# untitled.net
KiCad netlist of a schematic drawn in EAGLE
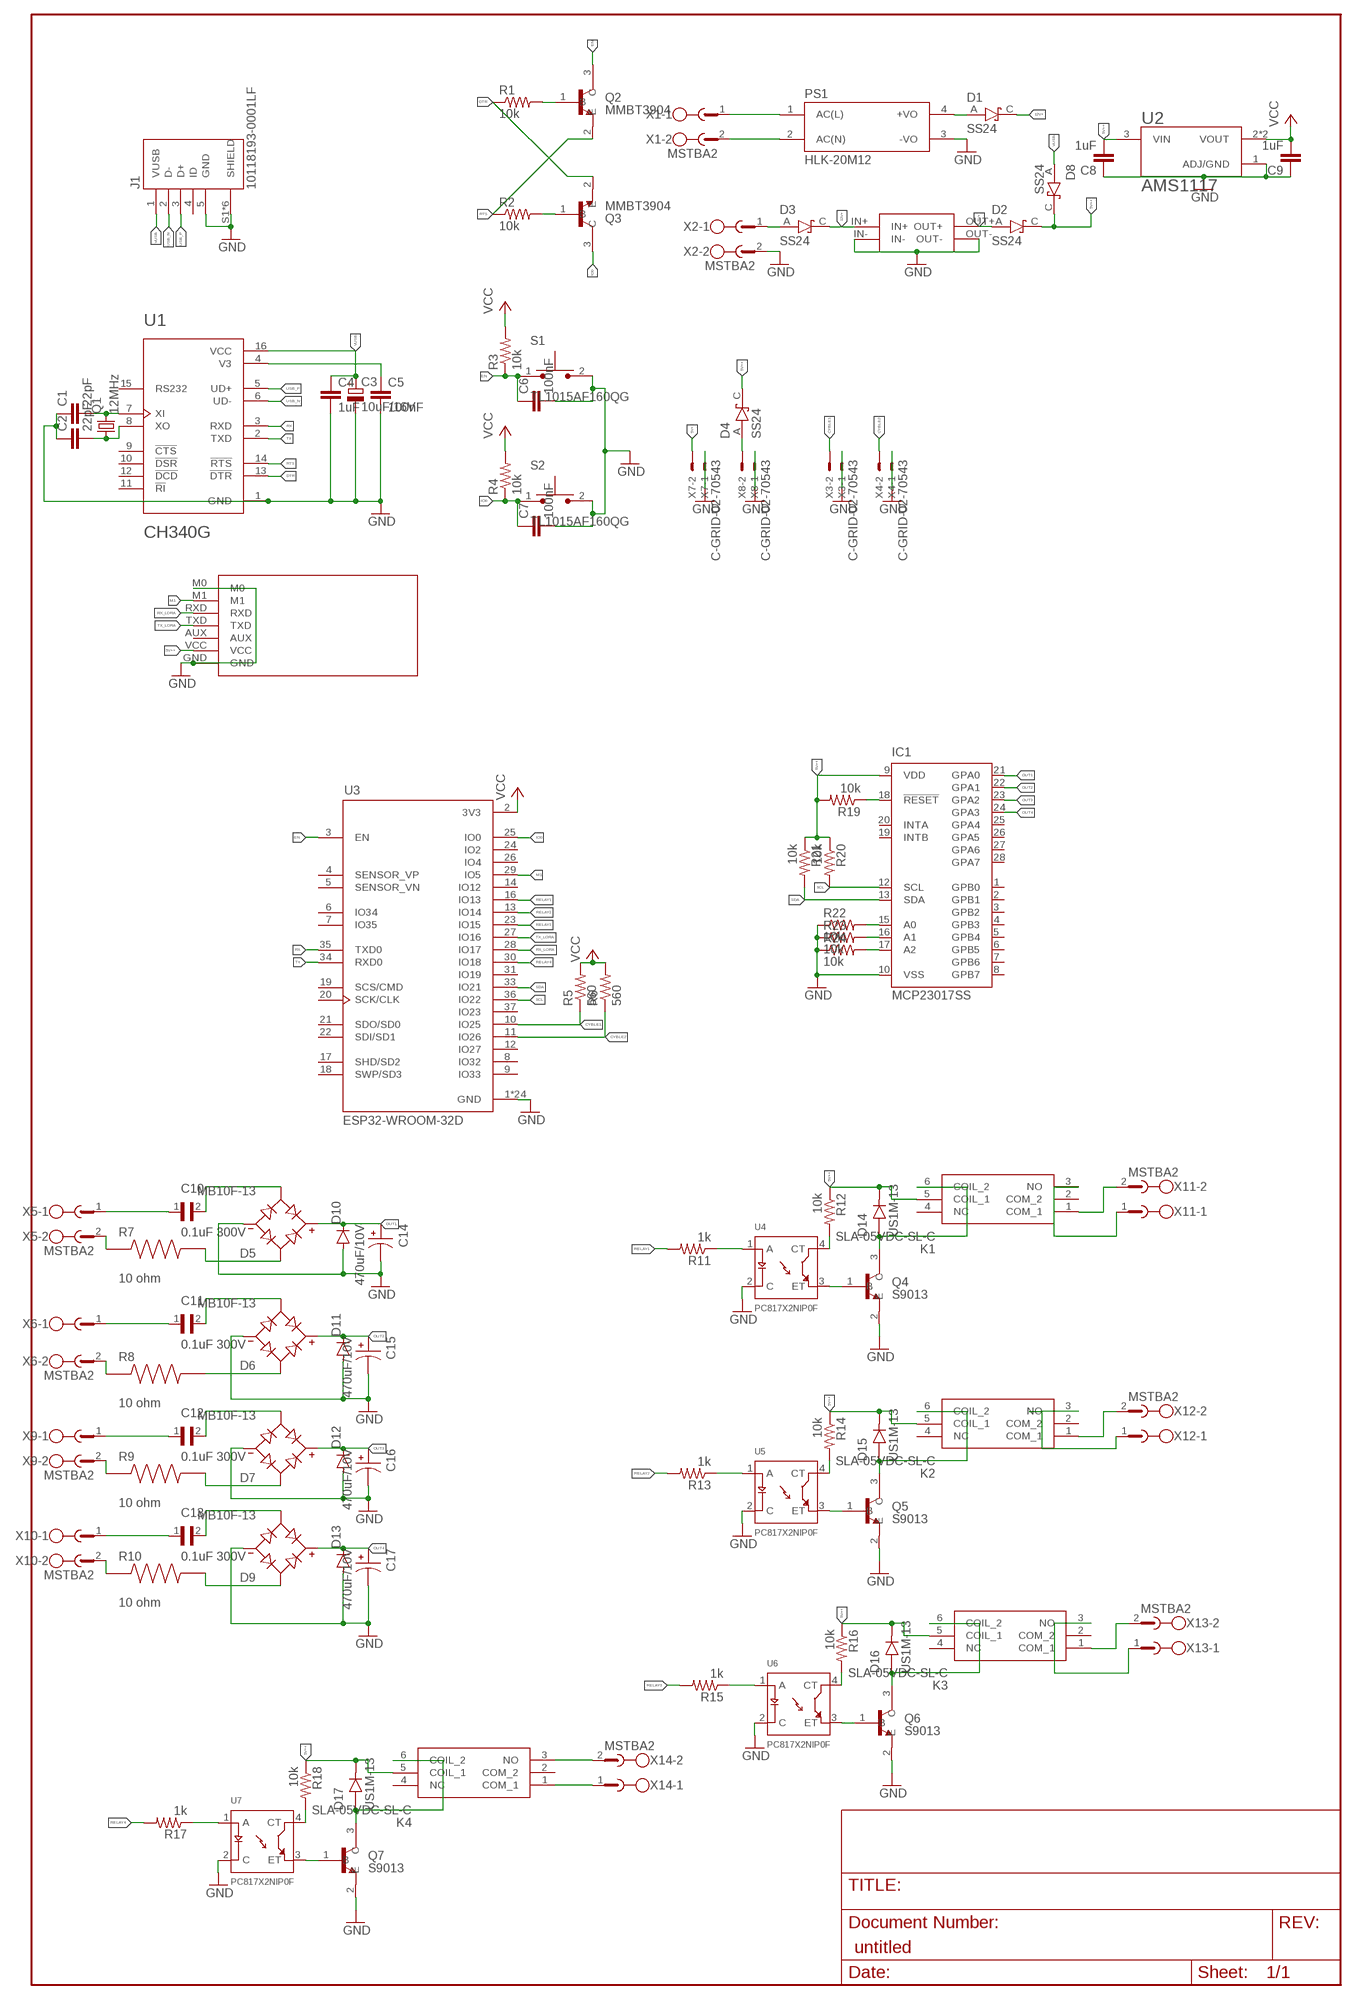
[diagram p0: schematic, sheet 1]

(export (version "E")
  (design (tool "Eeschema 10.0.6"))
  (components
    (comp (ref "C1")
      (value "22pF")
      (footprint "eagle-import:C0805K")
      (libsource (lib "eagle-import") (part "C-EUC0805K"))
    )
    (comp (ref "C2")
      (value "22pF")
      (footprint "eagle-import:C0805K")
      (libsource (lib "eagle-import") (part "C-EUC0805K"))
    )
    (comp (ref "C3")
      (value "10uF/16V")
      (footprint "eagle-import:153CLV-0505")
      (libsource (lib "eagle-import") (part "CPOL-EU153CLV-0505"))
    )
    (comp (ref "C4")
      (value "1uF")
      (footprint "eagle-import:C0805K")
      (libsource (lib "eagle-import") (part "C-EUC0805K"))
    )
    (comp (ref "C5")
      (value "100nF")
      (footprint "eagle-import:C0805K")
      (libsource (lib "eagle-import") (part "C-EUC0805K"))
    )
    (comp (ref "C6")
      (value "100nF")
      (footprint "eagle-import:C0805K")
      (libsource (lib "eagle-import") (part "C-EUC0805K"))
    )
    (comp (ref "C7")
      (value "100nF")
      (footprint "eagle-import:C0805K")
      (libsource (lib "eagle-import") (part "C-EUC0805K"))
    )
    (comp (ref "C8")
      (value "1uF")
      (footprint "eagle-import:C0805K")
      (libsource (lib "eagle-import") (part "C-EUC0805K"))
    )
    (comp (ref "C9")
      (value "1uF")
      (footprint "eagle-import:C0805K")
      (libsource (lib "eagle-import") (part "C-EUC0805K"))
    )
    (comp (ref "C10")
      (value "0.1uF 300V")
      (footprint "eagle-import:CAPRR1500W60L1750T500H1200")
      (fields (field (name "MF") "PANASONIC") (field (name "MP") "ECQ-UAAF104KA"))
      (libsource (lib "eagle-import") (part "ECQUAAF104KA"))
    )
    (comp (ref "C11")
      (value "0.1uF 300V")
      (footprint "eagle-import:CAPRR1500W60L1750T500H1200")
      (fields (field (name "MF") "PANASONIC") (field (name "MP") "ECQ-UAAF104KA"))
      (libsource (lib "eagle-import") (part "ECQUAAF104KA"))
    )
    (comp (ref "C12")
      (value "0.1uF 300V")
      (footprint "eagle-import:CAPRR1500W60L1750T500H1200")
      (fields (field (name "MF") "PANASONIC") (field (name "MP") "ECQ-UAAF104KA"))
      (libsource (lib "eagle-import") (part "ECQUAAF104KA"))
    )
    (comp (ref "C13")
      (value "0.1uF 300V")
      (footprint "eagle-import:CAPRR1500W60L1750T500H1200")
      (fields (field (name "MF") "PANASONIC") (field (name "MP") "ECQ-UAAF104KA"))
      (libsource (lib "eagle-import") (part "ECQUAAF104KA"))
    )
    (comp (ref "C14")
      (value "470uF/10V")
      (footprint "eagle-import:CAP_EEEFC1A471AP")
      (fields (field (name "MF") "Panasonic") (field (name "MP") "EEE-FC1A471AP"))
      (libsource (lib "eagle-import") (part "EEEFC1A471AP"))
    )
    (comp (ref "C15")
      (value "470uF/10V")
      (footprint "eagle-import:CAP_EEEFC1A471AP")
      (fields (field (name "MF") "Panasonic") (field (name "MP") "EEE-FC1A471AP"))
      (libsource (lib "eagle-import") (part "EEEFC1A471AP"))
    )
    (comp (ref "C16")
      (value "470uF/10V")
      (footprint "eagle-import:CAP_EEEFC1A471AP")
      (fields (field (name "MF") "Panasonic") (field (name "MP") "EEE-FC1A471AP"))
      (libsource (lib "eagle-import") (part "EEEFC1A471AP"))
    )
    (comp (ref "C17")
      (value "470uF/10V")
      (footprint "eagle-import:CAP_EEEFC1A471AP")
      (fields (field (name "MF") "Panasonic") (field (name "MP") "EEE-FC1A471AP"))
      (libsource (lib "eagle-import") (part "EEEFC1A471AP"))
    )
    (comp (ref "D1")
      (value "SS24")
      (footprint "eagle-import:DIOM5336X265N")
      (fields (field (name "MF") "ON Semiconductor"))
      (libsource (lib "eagle-import") (part "SS24"))
    )
    (comp (ref "D2")
      (value "SS24")
      (footprint "eagle-import:DIOM5336X265N")
      (fields (field (name "MF") "ON Semiconductor"))
      (libsource (lib "eagle-import") (part "SS24"))
    )
    (comp (ref "D3")
      (value "SS24")
      (footprint "eagle-import:DIOM5336X265N")
      (fields (field (name "MF") "ON Semiconductor"))
      (libsource (lib "eagle-import") (part "SS24"))
    )
    (comp (ref "D4")
      (value "SS24")
      (footprint "eagle-import:DIOM5336X265N")
      (fields (field (name "MF") "ON Semiconductor"))
      (libsource (lib "eagle-import") (part "SS24"))
    )
    (comp (ref "D5")
      (value "MB10F-13")
      (footprint "eagle-import:DIOB_MB10F-13")
      (fields (field (name "MF") "Diodes Inc."))
      (libsource (lib "eagle-import") (part "MB10F-13"))
    )
    (comp (ref "D6")
      (value "MB10F-13")
      (footprint "eagle-import:DIOB_MB10F-13")
      (fields (field (name "MF") "Diodes Inc."))
      (libsource (lib "eagle-import") (part "MB10F-13"))
    )
    (comp (ref "D7")
      (value "MB10F-13")
      (footprint "eagle-import:DIOB_MB10F-13")
      (fields (field (name "MF") "Diodes Inc."))
      (libsource (lib "eagle-import") (part "MB10F-13"))
    )
    (comp (ref "D8")
      (value "SS24")
      (footprint "eagle-import:DIOM5336X265N")
      (fields (field (name "MF") "ON Semiconductor"))
      (libsource (lib "eagle-import") (part "SS24"))
    )
    (comp (ref "D9")
      (value "MB10F-13")
      (footprint "eagle-import:DIOB_MB10F-13")
      (fields (field (name "MF") "Diodes Inc."))
      (libsource (lib "eagle-import") (part "MB10F-13"))
    )
    (comp (ref "D10")
      (value "DIODE-SOD123")
      (footprint "eagle-import:SOD123")
      (libsource (lib "eagle-import") (part "DIODE-SOD123"))
    )
    (comp (ref "D11")
      (value "DIODE-SOD123")
      (footprint "eagle-import:SOD123")
      (libsource (lib "eagle-import") (part "DIODE-SOD123"))
    )
    (comp (ref "D12")
      (value "DIODE-SOD123")
      (footprint "eagle-import:SOD123")
      (libsource (lib "eagle-import") (part "DIODE-SOD123"))
    )
    (comp (ref "D13")
      (value "DIODE-SOD123")
      (footprint "eagle-import:SOD123")
      (libsource (lib "eagle-import") (part "DIODE-SOD123"))
    )
    (comp (ref "D14")
      (value "US1M-13")
      (footprint "eagle-import:DIOM5226X240N")
      (fields (field (name "MF") "Diodes Incorporated"))
      (libsource (lib "eagle-import") (part "US1M-13"))
    )
    (comp (ref "D15")
      (value "US1M-13")
      (footprint "eagle-import:DIOM5226X240N")
      (fields (field (name "MF") "Diodes Incorporated"))
      (libsource (lib "eagle-import") (part "US1M-13"))
    )
    (comp (ref "D16")
      (value "US1M-13")
      (footprint "eagle-import:DIOM5226X240N")
      (fields (field (name "MF") "Diodes Incorporated"))
      (libsource (lib "eagle-import") (part "US1M-13"))
    )
    (comp (ref "D17")
      (value "US1M-13")
      (footprint "eagle-import:DIOM5226X240N")
      (fields (field (name "MF") "Diodes Incorporated"))
      (libsource (lib "eagle-import") (part "US1M-13"))
    )
    (comp (ref "EBYTEE220-900T22D1")
      (value "EBYTEE220-900T22D")
      (footprint "eagle-import:EBYTEE220-900T22D")
      (libsource (lib "eagle-import") (part "EBYTEE220-900T22D"))
    )
    (comp (ref "IC1")
      (value "MCP23017SS")
      (footprint "eagle-import:SSOP28")
      (libsource (lib "eagle-import") (part "MCP23017SS"))
    )
    (comp (ref "J1")
      (value "10118193-0001LF")
      (footprint "eagle-import:FCI_10118193-0001LF")
      (fields (field (name "MF") "FCI"))
      (libsource (lib "eagle-import") (part "10118193-0001LF"))
    )
    (comp (ref "K1")
      (value "SLA-05VDC-SL-C")
      (footprint "eagle-import:SLA05VDCSLC")
      (libsource (lib "eagle-import") (part "SLA-05VDC-SL-C"))
    )
    (comp (ref "K2")
      (value "SLA-05VDC-SL-C")
      (footprint "eagle-import:SLA05VDCSLC")
      (libsource (lib "eagle-import") (part "SLA-05VDC-SL-C"))
    )
    (comp (ref "K3")
      (value "SLA-05VDC-SL-C")
      (footprint "eagle-import:SLA05VDCSLC")
      (libsource (lib "eagle-import") (part "SLA-05VDC-SL-C"))
    )
    (comp (ref "K4")
      (value "SLA-05VDC-SL-C")
      (footprint "eagle-import:SLA05VDCSLC")
      (libsource (lib "eagle-import") (part "SLA-05VDC-SL-C"))
    )
    (comp (ref "MINI1")
      (value "MINI560")
      (footprint "eagle-import:MINI560")
      (libsource (lib "eagle-import") (part "MINI560"))
    )
    (comp (ref "PS1")
      (value "HLK-20M12")
      (footprint "eagle-import:CONV_HLK-20M12")
      (fields (field (name "MF") "Hi-link"))
      (libsource (lib "eagle-import") (part "HLK-20M12"))
    )
    (comp (ref "Q1")
      (value "12MHz")
      (footprint "eagle-import:SM49")
      (libsource (lib "eagle-import") (part "CRYSTALSM49"))
    )
    (comp (ref "Q2")
      (value "MMBT3904")
      (footprint "eagle-import:SOT95P240X120-3N")
      (fields (field (name "MF") "ON Semiconductor"))
      (libsource (lib "eagle-import") (part "MMBT3904"))
    )
    (comp (ref "Q3")
      (value "MMBT3904")
      (footprint "eagle-import:SOT95P240X120-3N")
      (fields (field (name "MF") "ON Semiconductor"))
      (libsource (lib "eagle-import") (part "MMBT3904"))
    )
    (comp (ref "Q4")
      (value "S9013")
      (footprint "eagle-import:SOT95P240X120-3N")
      (fields (field (name "MF") "JCET"))
      (libsource (lib "eagle-import") (part "S9013"))
    )
    (comp (ref "Q5")
      (value "S9013")
      (footprint "eagle-import:SOT95P240X120-3N")
      (fields (field (name "MF") "JCET"))
      (libsource (lib "eagle-import") (part "S9013"))
    )
    (comp (ref "Q6")
      (value "S9013")
      (footprint "eagle-import:SOT95P240X120-3N")
      (fields (field (name "MF") "JCET"))
      (libsource (lib "eagle-import") (part "S9013"))
    )
    (comp (ref "Q7")
      (value "S9013")
      (footprint "eagle-import:SOT95P240X120-3N")
      (fields (field (name "MF") "JCET"))
      (libsource (lib "eagle-import") (part "S9013"))
    )
    (comp (ref "R1")
      (value "10k")
      (footprint "eagle-import:M0805")
      (libsource (lib "eagle-import") (part "R-US_M0805"))
    )
    (comp (ref "R2")
      (value "10k")
      (footprint "eagle-import:M0805")
      (libsource (lib "eagle-import") (part "R-US_M0805"))
    )
    (comp (ref "R3")
      (value "10k")
      (footprint "eagle-import:M0805")
      (libsource (lib "eagle-import") (part "R-US_M0805"))
    )
    (comp (ref "R4")
      (value "10k")
      (footprint "eagle-import:M0805")
      (libsource (lib "eagle-import") (part "R-US_M0805"))
    )
    (comp (ref "R5")
      (value "560")
      (footprint "eagle-import:M0805")
      (libsource (lib "eagle-import") (part "R-US_M0805"))
    )
    (comp (ref "R6")
      (value "560")
      (footprint "eagle-import:M0805")
      (libsource (lib "eagle-import") (part "R-US_M0805"))
    )
    (comp (ref "R7")
      (value "10 ohm")
      (footprint "eagle-import:RES_ERJP14J200U")
      (fields (field (name "MF") "Panasonic") (field (name "MP") "ERJ-P14J200U"))
      (libsource (lib "eagle-import") (part "ERJP14J200U"))
    )
    (comp (ref "R8")
      (value "10 ohm")
      (footprint "eagle-import:RES_ERJP14J200U")
      (fields (field (name "MF") "Panasonic") (field (name "MP") "ERJ-P14J200U"))
      (libsource (lib "eagle-import") (part "ERJP14J200U"))
    )
    (comp (ref "R9")
      (value "10 ohm")
      (footprint "eagle-import:RES_ERJP14J200U")
      (fields (field (name "MF") "Panasonic") (field (name "MP") "ERJ-P14J200U"))
      (libsource (lib "eagle-import") (part "ERJP14J200U"))
    )
    (comp (ref "R10")
      (value "10 ohm")
      (footprint "eagle-import:RES_ERJP14J200U")
      (fields (field (name "MF") "Panasonic") (field (name "MP") "ERJ-P14J200U"))
      (libsource (lib "eagle-import") (part "ERJP14J200U"))
    )
    (comp (ref "R11")
      (value "1k")
      (footprint "eagle-import:M0805")
      (libsource (lib "eagle-import") (part "R-US_M0805"))
    )
    (comp (ref "R12")
      (value "10k")
      (footprint "eagle-import:M0805")
      (libsource (lib "eagle-import") (part "R-US_M0805"))
    )
    (comp (ref "R13")
      (value "1k")
      (footprint "eagle-import:M0805")
      (libsource (lib "eagle-import") (part "R-US_M0805"))
    )
    (comp (ref "R14")
      (value "10k")
      (footprint "eagle-import:M0805")
      (libsource (lib "eagle-import") (part "R-US_M0805"))
    )
    (comp (ref "R15")
      (value "1k")
      (footprint "eagle-import:M0805")
      (libsource (lib "eagle-import") (part "R-US_M0805"))
    )
    (comp (ref "R16")
      (value "10k")
      (footprint "eagle-import:M0805")
      (libsource (lib "eagle-import") (part "R-US_M0805"))
    )
    (comp (ref "R17")
      (value "1k")
      (footprint "eagle-import:M0805")
      (libsource (lib "eagle-import") (part "R-US_M0805"))
    )
    (comp (ref "R18")
      (value "10k")
      (footprint "eagle-import:M0805")
      (libsource (lib "eagle-import") (part "R-US_M0805"))
    )
    (comp (ref "R19")
      (value "10k")
      (footprint "eagle-import:M0805")
      (libsource (lib "eagle-import") (part "R-US_M0805"))
    )
    (comp (ref "R20")
      (value "10k")
      (footprint "eagle-import:M0805")
      (libsource (lib "eagle-import") (part "R-US_M0805"))
    )
    (comp (ref "R21")
      (value "10k")
      (footprint "eagle-import:M0805")
      (libsource (lib "eagle-import") (part "R-US_M0805"))
    )
    (comp (ref "R22")
      (value "10k")
      (footprint "eagle-import:M0805")
      (libsource (lib "eagle-import") (part "R-US_M0805"))
    )
    (comp (ref "R23")
      (value "10k")
      (footprint "eagle-import:M0805")
      (libsource (lib "eagle-import") (part "R-US_M0805"))
    )
    (comp (ref "R24")
      (value "10k")
      (footprint "eagle-import:M0805")
      (libsource (lib "eagle-import") (part "R-US_M0805"))
    )
    (comp (ref "S1")
      (value "TL1015AF160QG")
      (footprint "eagle-import:SW_TL1015AF160QG")
      (fields (field (name "MF") "E-Switch"))
      (libsource (lib "eagle-import") (part "TL1015AF160QG"))
    )
    (comp (ref "S2")
      (value "TL1015AF160QG")
      (footprint "eagle-import:SW_TL1015AF160QG")
      (fields (field (name "MF") "E-Switch"))
      (libsource (lib "eagle-import") (part "TL1015AF160QG"))
    )
    (comp (ref "U1")
      (value "CH340G")
      (footprint "eagle-import:SOIC127P600X180-16N")
      (fields (field (name "MF") "WCH") (field (name "MP") "Ch340G"))
      (libsource (lib "eagle-import") (part "CH340G"))
    )
    (comp (ref "U2")
      (value "AMS1117")
      (footprint "eagle-import:SOT229P700X180-4N")
      (fields (field (name "MF") "Advanced Monolithic Systems"))
      (libsource (lib "eagle-import") (part "AMS1117"))
    )
    (comp (ref "U3")
      (value "ESP32-WROOM-32D")
      (footprint "eagle-import:MODULE_ESP32-WROOM-32D")
      (fields (field (name "MF") "Espressif Systems"))
      (libsource (lib "eagle-import") (part "ESP32-WROOM-32D"))
    )
    (comp (ref "U4")
      (value "PC817X2NIP0F")
      (footprint "eagle-import:SOT254P975X400-4N")
      (fields (field (name "MF") "Sharp Microelectronics"))
      (libsource (lib "eagle-import") (part "PC817X2NIP0F"))
    )
    (comp (ref "U5")
      (value "PC817X2NIP0F")
      (footprint "eagle-import:SOT254P975X400-4N")
      (fields (field (name "MF") "Sharp Microelectronics"))
      (libsource (lib "eagle-import") (part "PC817X2NIP0F"))
    )
    (comp (ref "U6")
      (value "PC817X2NIP0F")
      (footprint "eagle-import:SOT254P975X400-4N")
      (fields (field (name "MF") "Sharp Microelectronics"))
      (libsource (lib "eagle-import") (part "PC817X2NIP0F"))
    )
    (comp (ref "U7")
      (value "PC817X2NIP0F")
      (footprint "eagle-import:SOT254P975X400-4N")
      (fields (field (name "MF") "Sharp Microelectronics"))
      (libsource (lib "eagle-import") (part "PC817X2NIP0F"))
    )
    (comp (ref "X1")
      (value "MSTBA2")
      (footprint "eagle-import:MSTBA2")
      (fields (field (name "MF") "FARNELL") (field (name "MPN") "1757242"))
      (libsource (lib "eagle-import") (part "MSTBA2"))
    )
    (comp (ref "X2")
      (value "MSTBA2")
      (footprint "eagle-import:MSTBA2")
      (fields (field (name "MF") "FARNELL") (field (name "MPN") "1757242"))
      (libsource (lib "eagle-import") (part "MSTBA2"))
    )
    (comp (ref "X3")
      (value "C-GRID-02-70543")
      (footprint "eagle-import:70543-02")
      (fields (field (name "MF") "MOLEX"))
      (libsource (lib "eagle-import") (part "C-GRID-02-70543"))
    )
    (comp (ref "X4")
      (value "C-GRID-02-70543")
      (footprint "eagle-import:70543-02")
      (fields (field (name "MF") "MOLEX"))
      (libsource (lib "eagle-import") (part "C-GRID-02-70543"))
    )
    (comp (ref "X5")
      (value "MSTBA2")
      (footprint "eagle-import:MSTBA2")
      (fields (field (name "MF") "FARNELL") (field (name "MPN") "1757242"))
      (libsource (lib "eagle-import") (part "MSTBA2"))
    )
    (comp (ref "X6")
      (value "MSTBA2")
      (footprint "eagle-import:MSTBA2")
      (fields (field (name "MF") "FARNELL") (field (name "MPN") "1757242"))
      (libsource (lib "eagle-import") (part "MSTBA2"))
    )
    (comp (ref "X7")
      (value "C-GRID-02-70543")
      (footprint "eagle-import:70543-02")
      (fields (field (name "MF") "MOLEX"))
      (libsource (lib "eagle-import") (part "C-GRID-02-70543"))
    )
    (comp (ref "X8")
      (value "C-GRID-02-70543")
      (footprint "eagle-import:70543-02")
      (fields (field (name "MF") "MOLEX"))
      (libsource (lib "eagle-import") (part "C-GRID-02-70543"))
    )
    (comp (ref "X9")
      (value "MSTBA2")
      (footprint "eagle-import:MSTBA2")
      (fields (field (name "MF") "FARNELL") (field (name "MPN") "1757242"))
      (libsource (lib "eagle-import") (part "MSTBA2"))
    )
    (comp (ref "X10")
      (value "MSTBA2")
      (footprint "eagle-import:MSTBA2")
      (fields (field (name "MF") "FARNELL") (field (name "MPN") "1757242"))
      (libsource (lib "eagle-import") (part "MSTBA2"))
    )
    (comp (ref "X11")
      (value "MSTBA2")
      (footprint "eagle-import:MSTBA2")
      (fields (field (name "MF") "FARNELL") (field (name "MPN") "1757242"))
      (libsource (lib "eagle-import") (part "MSTBA2"))
    )
    (comp (ref "X12")
      (value "MSTBA2")
      (footprint "eagle-import:MSTBA2")
      (fields (field (name "MF") "FARNELL") (field (name "MPN") "1757242"))
      (libsource (lib "eagle-import") (part "MSTBA2"))
    )
    (comp (ref "X13")
      (value "MSTBA2")
      (footprint "eagle-import:MSTBA2")
      (fields (field (name "MF") "FARNELL") (field (name "MPN") "1757242"))
      (libsource (lib "eagle-import") (part "MSTBA2"))
    )
    (comp (ref "X14")
      (value "MSTBA2")
      (footprint "eagle-import:MSTBA2")
      (fields (field (name "MF") "FARNELL") (field (name "MPN") "1757242"))
      (libsource (lib "eagle-import") (part "MSTBA2"))
    )
  )
  (nets
    (net (code "1") (name "5V+") (class "Default")
      (node (ref "D2") (pin "A") (pinfunction "A_A") (pintype "passive"))
      (node (ref "MINI1") (pin "OUT+") (pinfunction "OUT+_OUT+") (pintype "bidirectional"))
      (node (ref "X7") (pin "2") (pinfunction "S_2") (pintype "passive"))
    )
    (net (code "2") (name "5V++") (class "Default")
      (node (ref "C8") (pin "2") (pinfunction "2_2") (pintype "passive"))
      (node (ref "D14") (pin "C") (pinfunction "K_C") (pintype "passive"))
      (node (ref "D15") (pin "C") (pinfunction "K_C") (pintype "passive"))
      (node (ref "D16") (pin "C") (pinfunction "K_C") (pintype "passive"))
      (node (ref "D17") (pin "C") (pinfunction "K_C") (pintype "passive"))
      (node (ref "D2") (pin "C") (pinfunction "K_C") (pintype "passive"))
      (node (ref "D4") (pin "C") (pinfunction "K_C") (pintype "passive"))
      (node (ref "D8") (pin "C") (pinfunction "K_C") (pintype "passive"))
      (node (ref "EBYTEE220-900T22D1") (pin "VCC") (pinfunction "VCC_VCC") (pintype "bidirectional"))
      (node (ref "IC1") (pin "9") (pinfunction "VDD_9") (pintype "power_in"))
      (node (ref "K1") (pin "5") (pinfunction "COIL_1_5") (pintype "bidirectional"))
      (node (ref "K2") (pin "5") (pinfunction "COIL_1_5") (pintype "bidirectional"))
      (node (ref "K3") (pin "5") (pinfunction "COIL_1_5") (pintype "bidirectional"))
      (node (ref "K4") (pin "5") (pinfunction "COIL_1_5") (pintype "bidirectional"))
      (node (ref "R12") (pin "1") (pinfunction "1_1") (pintype "passive"))
      (node (ref "R14") (pin "1") (pinfunction "1_1") (pintype "passive"))
      (node (ref "R16") (pin "1") (pinfunction "1_1") (pintype "passive"))
      (node (ref "R18") (pin "1") (pinfunction "1_1") (pintype "passive"))
      (node (ref "R19") (pin "2") (pinfunction "2_2") (pintype "passive"))
      (node (ref "R20") (pin "1") (pinfunction "1_1") (pintype "passive"))
      (node (ref "R21") (pin "1") (pinfunction "1_1") (pintype "passive"))
      (node (ref "U2") (pin "3") (pinfunction "VIN_3") (pintype "input"))
    )
    (net (code "3") (name "12V+") (class "Default")
      (node (ref "D1") (pin "C") (pinfunction "K_C") (pintype "passive"))
      (node (ref "D3") (pin "C") (pinfunction "K_C") (pintype "passive"))
      (node (ref "MINI1") (pin "IN+") (pinfunction "IN+_IN+") (pintype "bidirectional"))
    )
    (net (code "4") (name "CYBLE1") (class "Default")
      (node (ref "R5") (pin "1") (pinfunction "1_1") (pintype "passive"))
      (node (ref "U3") (pin "10") (pinfunction "IO25_10") (pintype "bidirectional"))
      (node (ref "X3") (pin "2") (pinfunction "S_2") (pintype "passive"))
    )
    (net (code "5") (name "CYBLE2") (class "Default")
      (node (ref "R6") (pin "1") (pinfunction "1_1") (pintype "passive"))
      (node (ref "U3") (pin "11") (pinfunction "IO26_11") (pintype "bidirectional"))
      (node (ref "X4") (pin "2") (pinfunction "S_2") (pintype "passive"))
    )
    (net (code "6") (name "DTR") (class "Default")
      (node (ref "Q3") (pin "2") (pinfunction "E_2") (pintype "passive"))
      (node (ref "R1") (pin "1") (pinfunction "1_1") (pintype "passive"))
      (node (ref "U1") (pin "13") (pinfunction "~{DTR}_13") (pintype "output"))
    )
    (net (code "7") (name "EN") (class "Default")
      (node (ref "C6") (pin "1") (pinfunction "1_1") (pintype "passive"))
      (node (ref "Q2") (pin "3") (pinfunction "C_3") (pintype "passive"))
      (node (ref "R3") (pin "1") (pinfunction "1_1") (pintype "passive"))
      (node (ref "S1") (pin "1") (pinfunction "1_1") (pintype "passive"))
      (node (ref "U3") (pin "3") (pinfunction "EN_3") (pintype "input"))
    )
    (net (code "8") (name "GND") (class "Default")
      (node (ref "C1") (pin "1") (pinfunction "1_1") (pintype "passive"))
      (node (ref "C14") (pin "2") (pinfunction "2_2") (pintype "passive"))
      (node (ref "C15") (pin "2") (pinfunction "2_2") (pintype "passive"))
      (node (ref "C16") (pin "2") (pinfunction "2_2") (pintype "passive"))
      (node (ref "C17") (pin "2") (pinfunction "2_2") (pintype "passive"))
      (node (ref "C2") (pin "1") (pinfunction "1_1") (pintype "passive"))
      (node (ref "C3") (pin "-") (pinfunction "-_-") (pintype "passive"))
      (node (ref "C4") (pin "2") (pinfunction "2_2") (pintype "passive"))
      (node (ref "C5") (pin "2") (pinfunction "2_2") (pintype "passive"))
      (node (ref "C6") (pin "2") (pinfunction "2_2") (pintype "passive"))
      (node (ref "C7") (pin "2") (pinfunction "2_2") (pintype "passive"))
      (node (ref "C8") (pin "1") (pinfunction "1_1") (pintype "passive"))
      (node (ref "C9") (pin "1") (pinfunction "1_1") (pintype "passive"))
      (node (ref "D10") (pin "A") (pinfunction "A_A") (pintype "passive"))
      (node (ref "D11") (pin "A") (pinfunction "A_A") (pintype "passive"))
      (node (ref "D12") (pin "A") (pinfunction "A_A") (pintype "passive"))
      (node (ref "D13") (pin "A") (pinfunction "A_A") (pintype "passive"))
      (node (ref "D5") (pin "3") (pinfunction "-_3") (pintype "passive"))
      (node (ref "D6") (pin "3") (pinfunction "-_3") (pintype "passive"))
      (node (ref "D7") (pin "3") (pinfunction "-_3") (pintype "passive"))
      (node (ref "D9") (pin "3") (pinfunction "-_3") (pintype "passive"))
      (node (ref "EBYTEE220-900T22D1") (pin "GND") (pinfunction "GND_GND") (pintype "bidirectional"))
      (node (ref "EBYTEE220-900T22D1") (pin "M0") (pinfunction "M0_M0") (pintype "bidirectional"))
      (node (ref "IC1") (pin "10") (pinfunction "VSS_10") (pintype "power_in"))
      (node (ref "J1") (pin "5") (pinfunction "GND_5") (pintype "passive"))
      (node (ref "J1") (pin "S1") (pinfunction "SHIELD_S1") (pintype "passive"))
      (node (ref "J1") (pin "S2") (pinfunction "SHIELD_S2") (pintype "passive"))
      (node (ref "J1") (pin "S3") (pinfunction "SHIELD_S3") (pintype "passive"))
      (node (ref "J1") (pin "S4") (pinfunction "SHIELD_S4") (pintype "passive"))
      (node (ref "J1") (pin "S5") (pinfunction "SHIELD_S5") (pintype "passive"))
      (node (ref "J1") (pin "S6") (pinfunction "SHIELD_S6") (pintype "passive"))
      (node (ref "MINI1") (pin "IN-") (pinfunction "IN-_IN-") (pintype "bidirectional"))
      (node (ref "MINI1") (pin "OUT-") (pinfunction "OUT-_OUT-") (pintype "bidirectional"))
      (node (ref "PS1") (pin "3") (pinfunction "-VO_3") (pintype "output"))
      (node (ref "Q4") (pin "2") (pinfunction "E_2") (pintype "passive"))
      (node (ref "Q5") (pin "2") (pinfunction "E_2") (pintype "passive"))
      (node (ref "Q6") (pin "2") (pinfunction "E_2") (pintype "passive"))
      (node (ref "Q7") (pin "2") (pinfunction "E_2") (pintype "passive"))
      (node (ref "R22") (pin "1") (pinfunction "1_1") (pintype "passive"))
      (node (ref "R23") (pin "1") (pinfunction "1_1") (pintype "passive"))
      (node (ref "R24") (pin "1") (pinfunction "1_1") (pintype "passive"))
      (node (ref "S1") (pin "2") (pinfunction "2_2") (pintype "passive"))
      (node (ref "S2") (pin "2") (pinfunction "2_2") (pintype "passive"))
      (node (ref "U1") (pin "1") (pinfunction "GND_1") (pintype "power_in"))
      (node (ref "U2") (pin "1") (pinfunction "ADJ/GND_1") (pintype "power_in"))
      (node (ref "U3") (pin "1") (pinfunction "GND_1") (pintype "power_in"))
      (node (ref "U3") (pin "15") (pinfunction "GND_15") (pintype "power_in"))
      (node (ref "U3") (pin "38") (pinfunction "GND_38") (pintype "power_in"))
      (node (ref "U3") (pin "39_1") (pinfunction "GND_39_1") (pintype "power_in"))
      (node (ref "U3") (pin "39_10") (pinfunction "GND_39_10") (pintype "power_in"))
      (node (ref "U3") (pin "39_11") (pinfunction "GND_39_11") (pintype "power_in"))
      (node (ref "U3") (pin "39_12") (pinfunction "GND_39_12") (pintype "power_in"))
      (node (ref "U3") (pin "39_13") (pinfunction "GND_39_13") (pintype "power_in"))
      (node (ref "U3") (pin "39_14") (pinfunction "GND_39_14") (pintype "power_in"))
      (node (ref "U3") (pin "39_15") (pinfunction "GND_39_15") (pintype "power_in"))
      (node (ref "U3") (pin "39_16") (pinfunction "GND_39_16") (pintype "power_in"))
      (node (ref "U3") (pin "39_17") (pinfunction "GND_39_17") (pintype "power_in"))
      (node (ref "U3") (pin "39_18") (pinfunction "GND_39_18") (pintype "power_in"))
      (node (ref "U3") (pin "39_19") (pinfunction "GND_39_19") (pintype "power_in"))
      (node (ref "U3") (pin "39_2") (pinfunction "GND_39_2") (pintype "power_in"))
      (node (ref "U3") (pin "39_20") (pinfunction "GND_39_20") (pintype "power_in"))
      (node (ref "U3") (pin "39_21") (pinfunction "GND_39_21") (pintype "power_in"))
      (node (ref "U3") (pin "39_3") (pinfunction "GND_39_3") (pintype "power_in"))
      (node (ref "U3") (pin "39_4") (pinfunction "GND_39_4") (pintype "power_in"))
      (node (ref "U3") (pin "39_5") (pinfunction "GND_39_5") (pintype "power_in"))
      (node (ref "U3") (pin "39_6") (pinfunction "GND_39_6") (pintype "power_in"))
      (node (ref "U3") (pin "39_7") (pinfunction "GND_39_7") (pintype "power_in"))
      (node (ref "U3") (pin "39_8") (pinfunction "GND_39_8") (pintype "power_in"))
      (node (ref "U3") (pin "39_9") (pinfunction "GND_39_9") (pintype "power_in"))
      (node (ref "U4") (pin "2") (pinfunction "C_2") (pintype "passive"))
      (node (ref "U5") (pin "2") (pinfunction "C_2") (pintype "passive"))
      (node (ref "U6") (pin "2") (pinfunction "C_2") (pintype "passive"))
      (node (ref "U7") (pin "2") (pinfunction "C_2") (pintype "passive"))
      (node (ref "X2") (pin "2") (pinfunction "1_2") (pintype "passive"))
      (node (ref "X3") (pin "1") (pinfunction "S_1") (pintype "passive"))
      (node (ref "X4") (pin "1") (pinfunction "S_1") (pintype "passive"))
      (node (ref "X7") (pin "1") (pinfunction "S_1") (pintype "passive"))
      (node (ref "X8") (pin "1") (pinfunction "S_1") (pintype "passive"))
    )
    (net (code "9") (name "IO0") (class "Default")
      (node (ref "C7") (pin "1") (pinfunction "1_1") (pintype "passive"))
      (node (ref "Q3") (pin "3") (pinfunction "C_3") (pintype "passive"))
      (node (ref "R4") (pin "1") (pinfunction "1_1") (pintype "passive"))
      (node (ref "S2") (pin "1") (pinfunction "1_1") (pintype "passive"))
      (node (ref "U3") (pin "25") (pinfunction "IO0_25") (pintype "bidirectional"))
    )
    (net (code "10") (name "M1") (class "Default")
      (node (ref "EBYTEE220-900T22D1") (pin "M1") (pinfunction "M1_M1") (pintype "bidirectional"))
      (node (ref "U3") (pin "29") (pinfunction "IO5_29") (pintype "bidirectional"))
    )
    (net (code "11") (name "Net-(C10-Pad1)") (class "Default")
      (node (ref "C10") (pin "1") (pinfunction "1_1") (pintype "passive"))
      (node (ref "X5") (pin "1") (pinfunction "1_1") (pintype "passive"))
    )
    (net (code "12") (name "Net-(C11-Pad1)") (class "Default")
      (node (ref "C11") (pin "1") (pinfunction "1_1") (pintype "passive"))
      (node (ref "X6") (pin "1") (pinfunction "1_1") (pintype "passive"))
    )
    (net (code "13") (name "Net-(C12-Pad1)") (class "Default")
      (node (ref "C12") (pin "1") (pinfunction "1_1") (pintype "passive"))
      (node (ref "X9") (pin "1") (pinfunction "1_1") (pintype "passive"))
    )
    (net (code "14") (name "Net-(C13-Pad1)") (class "Default")
      (node (ref "C13") (pin "1") (pinfunction "1_1") (pintype "passive"))
      (node (ref "X10") (pin "1") (pinfunction "1_1") (pintype "passive"))
    )
    (net (code "15") (name "Net-(D3-PadA)") (class "Default")
      (node (ref "D3") (pin "A") (pinfunction "A_A") (pintype "passive"))
      (node (ref "X2") (pin "1") (pinfunction "1_1") (pintype "passive"))
    )
    (net (code "16") (name "Net-(D5-AC1)") (class "Default")
      (node (ref "D5") (pin "2") (pinfunction "AC1_2") (pintype "passive"))
      (node (ref "R7") (pin "2") (pinfunction "2_2") (pintype "passive"))
    )
    (net (code "17") (name "Net-(D5-AC2)") (class "Default")
      (node (ref "C10") (pin "2") (pinfunction "2_2") (pintype "passive"))
      (node (ref "D5") (pin "4") (pinfunction "AC2_4") (pintype "passive"))
    )
    (net (code "18") (name "Net-(D6-AC1)") (class "Default")
      (node (ref "D6") (pin "2") (pinfunction "AC1_2") (pintype "passive"))
      (node (ref "R8") (pin "2") (pinfunction "2_2") (pintype "passive"))
    )
    (net (code "19") (name "Net-(D6-AC2)") (class "Default")
      (node (ref "C11") (pin "2") (pinfunction "2_2") (pintype "passive"))
      (node (ref "D6") (pin "4") (pinfunction "AC2_4") (pintype "passive"))
    )
    (net (code "20") (name "Net-(D7-AC1)") (class "Default")
      (node (ref "D7") (pin "2") (pinfunction "AC1_2") (pintype "passive"))
      (node (ref "R9") (pin "2") (pinfunction "2_2") (pintype "passive"))
    )
    (net (code "21") (name "Net-(D7-AC2)") (class "Default")
      (node (ref "C12") (pin "2") (pinfunction "2_2") (pintype "passive"))
      (node (ref "D7") (pin "4") (pinfunction "AC2_4") (pintype "passive"))
    )
    (net (code "22") (name "Net-(D9-AC1)") (class "Default")
      (node (ref "D9") (pin "2") (pinfunction "AC1_2") (pintype "passive"))
      (node (ref "R10") (pin "2") (pinfunction "2_2") (pintype "passive"))
    )
    (net (code "23") (name "Net-(D9-AC2)") (class "Default")
      (node (ref "C13") (pin "2") (pinfunction "2_2") (pintype "passive"))
      (node (ref "D9") (pin "4") (pinfunction "AC2_4") (pintype "passive"))
    )
    (net (code "24") (name "Net-(IC1-A0)") (class "Default")
      (node (ref "IC1") (pin "15") (pinfunction "A0_15") (pintype "input"))
      (node (ref "R22") (pin "2") (pinfunction "2_2") (pintype "passive"))
    )
    (net (code "25") (name "Net-(IC1-A1)") (class "Default")
      (node (ref "IC1") (pin "16") (pinfunction "A1_16") (pintype "input"))
      (node (ref "R23") (pin "2") (pinfunction "2_2") (pintype "passive"))
    )
    (net (code "26") (name "Net-(IC1-A2)") (class "Default")
      (node (ref "IC1") (pin "17") (pinfunction "A2_17") (pintype "input"))
      (node (ref "R24") (pin "2") (pinfunction "2_2") (pintype "passive"))
    )
    (net (code "27") (name "Net-(IC1-~{RESET})") (class "Default")
      (node (ref "IC1") (pin "18") (pinfunction "~{RESET}_18") (pintype "input"))
      (node (ref "R19") (pin "1") (pinfunction "1_1") (pintype "passive"))
    )
    (net (code "28") (name "Net-(K1-COIL_2)") (class "Default")
      (node (ref "D14") (pin "A") (pinfunction "A_A") (pintype "passive"))
      (node (ref "K1") (pin "6") (pinfunction "COIL_2_6") (pintype "bidirectional"))
      (node (ref "Q4") (pin "3") (pinfunction "C_3") (pintype "passive"))
    )
    (net (code "29") (name "Net-(K1-COM_1)") (class "Default")
      (node (ref "K1") (pin "1") (pinfunction "COM_1_1") (pintype "bidirectional"))
      (node (ref "X11") (pin "2") (pinfunction "1_2") (pintype "passive"))
    )
    (net (code "30") (name "Net-(K1-NO)") (class "Default")
      (node (ref "K1") (pin "3") (pinfunction "NO_3") (pintype "bidirectional"))
      (node (ref "X11") (pin "1") (pinfunction "1_1") (pintype "passive"))
    )
    (net (code "31") (name "Net-(K2-COIL_2)") (class "Default")
      (node (ref "D15") (pin "A") (pinfunction "A_A") (pintype "passive"))
      (node (ref "K2") (pin "6") (pinfunction "COIL_2_6") (pintype "bidirectional"))
      (node (ref "Q5") (pin "3") (pinfunction "C_3") (pintype "passive"))
    )
    (net (code "32") (name "Net-(K2-COM_1)") (class "Default")
      (node (ref "K2") (pin "1") (pinfunction "COM_1_1") (pintype "bidirectional"))
      (node (ref "X12") (pin "2") (pinfunction "1_2") (pintype "passive"))
    )
    (net (code "33") (name "Net-(K2-NO)") (class "Default")
      (node (ref "K2") (pin "3") (pinfunction "NO_3") (pintype "bidirectional"))
      (node (ref "X12") (pin "1") (pinfunction "1_1") (pintype "passive"))
    )
    (net (code "34") (name "Net-(K3-COIL_2)") (class "Default")
      (node (ref "D16") (pin "A") (pinfunction "A_A") (pintype "passive"))
      (node (ref "K3") (pin "6") (pinfunction "COIL_2_6") (pintype "bidirectional"))
      (node (ref "Q6") (pin "3") (pinfunction "C_3") (pintype "passive"))
    )
    (net (code "35") (name "Net-(K3-COM_1)") (class "Default")
      (node (ref "K3") (pin "1") (pinfunction "COM_1_1") (pintype "bidirectional"))
      (node (ref "X13") (pin "2") (pinfunction "1_2") (pintype "passive"))
    )
    (net (code "36") (name "Net-(K3-NO)") (class "Default")
      (node (ref "K3") (pin "3") (pinfunction "NO_3") (pintype "bidirectional"))
      (node (ref "X13") (pin "1") (pinfunction "1_1") (pintype "passive"))
    )
    (net (code "37") (name "Net-(K4-COIL_2)") (class "Default")
      (node (ref "D17") (pin "A") (pinfunction "A_A") (pintype "passive"))
      (node (ref "K4") (pin "6") (pinfunction "COIL_2_6") (pintype "bidirectional"))
      (node (ref "Q7") (pin "3") (pinfunction "C_3") (pintype "passive"))
    )
    (net (code "38") (name "Net-(K4-COM_1)") (class "Default")
      (node (ref "K4") (pin "1") (pinfunction "COM_1_1") (pintype "bidirectional"))
      (node (ref "X14") (pin "1") (pinfunction "1_1") (pintype "passive"))
    )
    (net (code "39") (name "Net-(K4-NO)") (class "Default")
      (node (ref "K4") (pin "3") (pinfunction "NO_3") (pintype "bidirectional"))
      (node (ref "X14") (pin "2") (pinfunction "1_2") (pintype "passive"))
    )
    (net (code "40") (name "Net-(PS1-+VO)") (class "Default")
      (node (ref "D1") (pin "A") (pinfunction "A_A") (pintype "passive"))
      (node (ref "PS1") (pin "4") (pinfunction "+VO_4") (pintype "output"))
    )
    (net (code "41") (name "Net-(PS1-AC(L))") (class "Default")
      (node (ref "PS1") (pin "1") (pinfunction "AC(L)_1") (pintype "input"))
      (node (ref "X1") (pin "1") (pinfunction "1_1") (pintype "passive"))
    )
    (net (code "42") (name "Net-(PS1-AC(N))") (class "Default")
      (node (ref "PS1") (pin "2") (pinfunction "AC(N)_2") (pintype "input"))
      (node (ref "X1") (pin "2") (pinfunction "1_2") (pintype "passive"))
    )
    (net (code "43") (name "Net-(Q2-B)") (class "Default")
      (node (ref "Q2") (pin "1") (pinfunction "B_1") (pintype "passive"))
      (node (ref "R1") (pin "2") (pinfunction "2_2") (pintype "passive"))
    )
    (net (code "44") (name "Net-(Q3-B)") (class "Default")
      (node (ref "Q3") (pin "1") (pinfunction "B_1") (pintype "passive"))
      (node (ref "R2") (pin "2") (pinfunction "2_2") (pintype "passive"))
    )
    (net (code "45") (name "Net-(Q4-B)") (class "Default")
      (node (ref "Q4") (pin "1") (pinfunction "B_1") (pintype "passive"))
      (node (ref "U4") (pin "3") (pinfunction "ET_3") (pintype "passive"))
    )
    (net (code "46") (name "Net-(Q5-B)") (class "Default")
      (node (ref "Q5") (pin "1") (pinfunction "B_1") (pintype "passive"))
      (node (ref "U5") (pin "3") (pinfunction "ET_3") (pintype "passive"))
    )
    (net (code "47") (name "Net-(Q6-B)") (class "Default")
      (node (ref "Q6") (pin "1") (pinfunction "B_1") (pintype "passive"))
      (node (ref "U6") (pin "3") (pinfunction "ET_3") (pintype "passive"))
    )
    (net (code "48") (name "Net-(Q7-B)") (class "Default")
      (node (ref "Q7") (pin "1") (pinfunction "B_1") (pintype "passive"))
      (node (ref "U7") (pin "3") (pinfunction "ET_3") (pintype "passive"))
    )
    (net (code "49") (name "Net-(U1-V3)") (class "Default")
      (node (ref "C5") (pin "1") (pinfunction "1_1") (pintype "passive"))
      (node (ref "U1") (pin "4") (pinfunction "V3_4") (pintype "power_in"))
    )
    (net (code "50") (name "Net-(U1-XI)") (class "Default")
      (node (ref "C1") (pin "2") (pinfunction "2_2") (pintype "passive"))
      (node (ref "Q1") (pin "2") (pinfunction "2_2") (pintype "passive"))
      (node (ref "U1") (pin "7") (pinfunction "XI_7") (pintype "input"))
    )
    (net (code "51") (name "Net-(U1-XO)") (class "Default")
      (node (ref "C2") (pin "2") (pinfunction "2_2") (pintype "passive"))
      (node (ref "Q1") (pin "1") (pinfunction "1_1") (pintype "passive"))
      (node (ref "U1") (pin "8") (pinfunction "XO_8") (pintype "output"))
    )
    (net (code "52") (name "Net-(U4-A)") (class "Default")
      (node (ref "R11") (pin "1") (pinfunction "1_1") (pintype "passive"))
      (node (ref "U4") (pin "1") (pinfunction "A_1") (pintype "passive"))
    )
    (net (code "53") (name "Net-(U4-CT)") (class "Default")
      (node (ref "R12") (pin "2") (pinfunction "2_2") (pintype "passive"))
      (node (ref "U4") (pin "4") (pinfunction "CT_4") (pintype "passive"))
    )
    (net (code "54") (name "Net-(U5-A)") (class "Default")
      (node (ref "R13") (pin "1") (pinfunction "1_1") (pintype "passive"))
      (node (ref "U5") (pin "1") (pinfunction "A_1") (pintype "passive"))
    )
    (net (code "55") (name "Net-(U5-CT)") (class "Default")
      (node (ref "R14") (pin "2") (pinfunction "2_2") (pintype "passive"))
      (node (ref "U5") (pin "4") (pinfunction "CT_4") (pintype "passive"))
    )
    (net (code "56") (name "Net-(U6-A)") (class "Default")
      (node (ref "R15") (pin "1") (pinfunction "1_1") (pintype "passive"))
      (node (ref "U6") (pin "1") (pinfunction "A_1") (pintype "passive"))
    )
    (net (code "57") (name "Net-(U6-CT)") (class "Default")
      (node (ref "R16") (pin "2") (pinfunction "2_2") (pintype "passive"))
      (node (ref "U6") (pin "4") (pinfunction "CT_4") (pintype "passive"))
    )
    (net (code "58") (name "Net-(U7-A)") (class "Default")
      (node (ref "R17") (pin "1") (pinfunction "1_1") (pintype "passive"))
      (node (ref "U7") (pin "1") (pinfunction "A_1") (pintype "passive"))
    )
    (net (code "59") (name "Net-(U7-CT)") (class "Default")
      (node (ref "R18") (pin "2") (pinfunction "2_2") (pintype "passive"))
      (node (ref "U7") (pin "4") (pinfunction "CT_4") (pintype "passive"))
    )
    (net (code "60") (name "Net-(X5B-1)") (class "Default")
      (node (ref "R7") (pin "1") (pinfunction "1_1") (pintype "passive"))
      (node (ref "X5") (pin "2") (pinfunction "1_2") (pintype "passive"))
    )
    (net (code "61") (name "Net-(X6B-1)") (class "Default")
      (node (ref "R8") (pin "1") (pinfunction "1_1") (pintype "passive"))
      (node (ref "X6") (pin "2") (pinfunction "1_2") (pintype "passive"))
    )
    (net (code "62") (name "Net-(X8B-S)") (class "Default")
      (node (ref "D4") (pin "A") (pinfunction "A_A") (pintype "passive"))
      (node (ref "X8") (pin "2") (pinfunction "S_2") (pintype "passive"))
    )
    (net (code "63") (name "Net-(X9B-1)") (class "Default")
      (node (ref "R9") (pin "1") (pinfunction "1_1") (pintype "passive"))
      (node (ref "X9") (pin "2") (pinfunction "1_2") (pintype "passive"))
    )
    (net (code "64") (name "Net-(X10B-1)") (class "Default")
      (node (ref "R10") (pin "1") (pinfunction "1_1") (pintype "passive"))
      (node (ref "X10") (pin "2") (pinfunction "1_2") (pintype "passive"))
    )
    (net (code "65") (name "OUT1") (class "Default")
      (node (ref "C14") (pin "1") (pinfunction "1_1") (pintype "passive"))
      (node (ref "D10") (pin "C") (pinfunction "C_C") (pintype "passive"))
      (node (ref "D5") (pin "1") (pinfunction "+_1") (pintype "passive"))
      (node (ref "IC1") (pin "21") (pinfunction "GPA0_21") (pintype "bidirectional"))
    )
    (net (code "66") (name "OUT2") (class "Default")
      (node (ref "C15") (pin "1") (pinfunction "1_1") (pintype "passive"))
      (node (ref "D11") (pin "C") (pinfunction "C_C") (pintype "passive"))
      (node (ref "D6") (pin "1") (pinfunction "+_1") (pintype "passive"))
      (node (ref "IC1") (pin "22") (pinfunction "GPA1_22") (pintype "bidirectional"))
    )
    (net (code "67") (name "OUT3") (class "Default")
      (node (ref "C16") (pin "1") (pinfunction "1_1") (pintype "passive"))
      (node (ref "D12") (pin "C") (pinfunction "C_C") (pintype "passive"))
      (node (ref "D7") (pin "1") (pinfunction "+_1") (pintype "passive"))
      (node (ref "IC1") (pin "23") (pinfunction "GPA2_23") (pintype "bidirectional"))
    )
    (net (code "68") (name "OUT4") (class "Default")
      (node (ref "C17") (pin "1") (pinfunction "1_1") (pintype "passive"))
      (node (ref "D13") (pin "C") (pinfunction "C_C") (pintype "passive"))
      (node (ref "D9") (pin "1") (pinfunction "+_1") (pintype "passive"))
      (node (ref "IC1") (pin "24") (pinfunction "GPA3_24") (pintype "bidirectional"))
    )
    (net (code "69") (name "RELAY1") (class "Default")
      (node (ref "R11") (pin "2") (pinfunction "2_2") (pintype "passive"))
      (node (ref "U3") (pin "16") (pinfunction "IO13_16") (pintype "bidirectional"))
    )
    (net (code "70") (name "RELAY2") (class "Default")
      (node (ref "R13") (pin "2") (pinfunction "2_2") (pintype "passive"))
      (node (ref "U3") (pin "13") (pinfunction "IO14_13") (pintype "bidirectional"))
    )
    (net (code "71") (name "RELAY3") (class "Default")
      (node (ref "R15") (pin "2") (pinfunction "2_2") (pintype "passive"))
      (node (ref "U3") (pin "23") (pinfunction "IO15_23") (pintype "bidirectional"))
    )
    (net (code "72") (name "RELAY4") (class "Default")
      (node (ref "R17") (pin "2") (pinfunction "2_2") (pintype "passive"))
      (node (ref "U3") (pin "30") (pinfunction "IO18_30") (pintype "bidirectional"))
    )
    (net (code "73") (name "RTS") (class "Default")
      (node (ref "Q2") (pin "2") (pinfunction "E_2") (pintype "passive"))
      (node (ref "R2") (pin "1") (pinfunction "1_1") (pintype "passive"))
      (node (ref "U1") (pin "14") (pinfunction "~{RTS}_14") (pintype "output"))
    )
    (net (code "74") (name "RX") (class "Default")
      (node (ref "U1") (pin "3") (pinfunction "RXD_3") (pintype "input"))
      (node (ref "U3") (pin "35") (pinfunction "TXD0_35") (pintype "bidirectional"))
    )
    (net (code "75") (name "RX_LORA") (class "Default")
      (node (ref "EBYTEE220-900T22D1") (pin "RXD") (pinfunction "RXD_RXD") (pintype "bidirectional"))
      (node (ref "U3") (pin "28") (pinfunction "IO17_28") (pintype "bidirectional"))
    )
    (net (code "76") (name "SCL") (class "Default")
      (node (ref "IC1") (pin "12") (pinfunction "SCL_12") (pintype "input"))
      (node (ref "R20") (pin "2") (pinfunction "2_2") (pintype "passive"))
      (node (ref "U3") (pin "36") (pinfunction "IO22_36") (pintype "bidirectional"))
    )
    (net (code "77") (name "SDA") (class "Default")
      (node (ref "IC1") (pin "13") (pinfunction "SDA_13") (pintype "bidirectional"))
      (node (ref "R21") (pin "2") (pinfunction "2_2") (pintype "passive"))
      (node (ref "U3") (pin "33") (pinfunction "IO21_33") (pintype "bidirectional"))
    )
    (net (code "78") (name "TX") (class "Default")
      (node (ref "U1") (pin "2") (pinfunction "TXD_2") (pintype "output"))
      (node (ref "U3") (pin "34") (pinfunction "RXD0_34") (pintype "bidirectional"))
    )
    (net (code "79") (name "TX_LORA") (class "Default")
      (node (ref "EBYTEE220-900T22D1") (pin "TXD") (pinfunction "TXD_TXD") (pintype "bidirectional"))
      (node (ref "U3") (pin "27") (pinfunction "IO16_27") (pintype "bidirectional"))
    )
    (net (code "80") (name "USB_N") (class "Default")
      (node (ref "J1") (pin "2") (pinfunction "D-_2") (pintype "passive"))
      (node (ref "U1") (pin "6") (pinfunction "UD-_6") (pintype "bidirectional"))
    )
    (net (code "81") (name "USB_P") (class "Default")
      (node (ref "J1") (pin "3") (pinfunction "D+_3") (pintype "passive"))
      (node (ref "U1") (pin "5") (pinfunction "UD+_5") (pintype "bidirectional"))
    )
    (net (code "82") (name "VCC") (class "Default")
      (node (ref "C9") (pin "2") (pinfunction "2_2") (pintype "passive"))
      (node (ref "R3") (pin "2") (pinfunction "2_2") (pintype "passive"))
      (node (ref "R4") (pin "2") (pinfunction "2_2") (pintype "passive"))
      (node (ref "R5") (pin "2") (pinfunction "2_2") (pintype "passive"))
      (node (ref "R6") (pin "2") (pinfunction "2_2") (pintype "passive"))
      (node (ref "U2") (pin "2") (pinfunction "VOUT_2") (pintype "output"))
      (node (ref "U2") (pin "4") (pinfunction "VOUT_4") (pintype "output"))
      (node (ref "U3") (pin "2") (pinfunction "3V3_2") (pintype "power_in"))
    )
    (net (code "83") (name "VUSB") (class "Default")
      (node (ref "C3") (pin "+") (pinfunction "+_+") (pintype "passive"))
      (node (ref "C4") (pin "1") (pinfunction "1_1") (pintype "passive"))
      (node (ref "D8") (pin "A") (pinfunction "A_A") (pintype "passive"))
      (node (ref "J1") (pin "1") (pinfunction "VUSB_1") (pintype "passive"))
      (node (ref "U1") (pin "16") (pinfunction "VCC_16") (pintype "power_in"))
    )
    (net (code "84") (name "unconnected-(EBYTEE220-900T22D1-PadAUX)") (class "Default")
      (node (ref "EBYTEE220-900T22D1") (pin "AUX") (pinfunction "AUX_AUX") (pintype "bidirectional"))
    )
    (net (code "85") (name "unconnected-(IC1-GPA4-Pad25)") (class "Default")
      (node (ref "IC1") (pin "25") (pinfunction "GPA4_25") (pintype "bidirectional"))
    )
    (net (code "86") (name "unconnected-(IC1-GPA5-Pad26)") (class "Default")
      (node (ref "IC1") (pin "26") (pinfunction "GPA5_26") (pintype "bidirectional"))
    )
    (net (code "87") (name "unconnected-(IC1-GPA6-Pad27)") (class "Default")
      (node (ref "IC1") (pin "27") (pinfunction "GPA6_27") (pintype "bidirectional"))
    )
    (net (code "88") (name "unconnected-(IC1-GPA7-Pad28)") (class "Default")
      (node (ref "IC1") (pin "28") (pinfunction "GPA7_28") (pintype "bidirectional"))
    )
    (net (code "89") (name "unconnected-(IC1-GPB0-Pad1)") (class "Default")
      (node (ref "IC1") (pin "1") (pinfunction "GPB0_1") (pintype "bidirectional"))
    )
    (net (code "90") (name "unconnected-(IC1-GPB1-Pad2)") (class "Default")
      (node (ref "IC1") (pin "2") (pinfunction "GPB1_2") (pintype "bidirectional"))
    )
    (net (code "91") (name "unconnected-(IC1-GPB2-Pad3)") (class "Default")
      (node (ref "IC1") (pin "3") (pinfunction "GPB2_3") (pintype "bidirectional"))
    )
    (net (code "92") (name "unconnected-(IC1-GPB3-Pad4)") (class "Default")
      (node (ref "IC1") (pin "4") (pinfunction "GPB3_4") (pintype "bidirectional"))
    )
    (net (code "93") (name "unconnected-(IC1-GPB4-Pad5)") (class "Default")
      (node (ref "IC1") (pin "5") (pinfunction "GPB4_5") (pintype "bidirectional"))
    )
    (net (code "94") (name "unconnected-(IC1-GPB5-Pad6)") (class "Default")
      (node (ref "IC1") (pin "6") (pinfunction "GPB5_6") (pintype "bidirectional"))
    )
    (net (code "95") (name "unconnected-(IC1-GPB6-Pad7)") (class "Default")
      (node (ref "IC1") (pin "7") (pinfunction "GPB6_7") (pintype "bidirectional"))
    )
    (net (code "96") (name "unconnected-(IC1-GPB7-Pad8)") (class "Default")
      (node (ref "IC1") (pin "8") (pinfunction "GPB7_8") (pintype "bidirectional"))
    )
    (net (code "97") (name "unconnected-(IC1-INTA-Pad20)") (class "Default")
      (node (ref "IC1") (pin "20") (pinfunction "INTA_20") (pintype "output"))
    )
    (net (code "98") (name "unconnected-(IC1-INTB-Pad19)") (class "Default")
      (node (ref "IC1") (pin "19") (pinfunction "INTB_19") (pintype "output"))
    )
    (net (code "99") (name "unconnected-(J1-ID-Pad4)") (class "Default")
      (node (ref "J1") (pin "4") (pinfunction "ID_4") (pintype "passive"))
    )
    (net (code "100") (name "unconnected-(K1-COM_2-Pad2)") (class "Default")
      (node (ref "K1") (pin "2") (pinfunction "COM_2_2") (pintype "bidirectional"))
    )
    (net (code "101") (name "unconnected-(K1-NC-Pad4)") (class "Default")
      (node (ref "K1") (pin "4") (pinfunction "NC_4") (pintype "no_connect"))
    )
    (net (code "102") (name "unconnected-(K2-COM_2-Pad2)") (class "Default")
      (node (ref "K2") (pin "2") (pinfunction "COM_2_2") (pintype "bidirectional"))
    )
    (net (code "103") (name "unconnected-(K2-NC-Pad4)") (class "Default")
      (node (ref "K2") (pin "4") (pinfunction "NC_4") (pintype "no_connect"))
    )
    (net (code "104") (name "unconnected-(K3-COM_2-Pad2)") (class "Default")
      (node (ref "K3") (pin "2") (pinfunction "COM_2_2") (pintype "bidirectional"))
    )
    (net (code "105") (name "unconnected-(K3-NC-Pad4)") (class "Default")
      (node (ref "K3") (pin "4") (pinfunction "NC_4") (pintype "no_connect"))
    )
    (net (code "106") (name "unconnected-(K4-COM_2-Pad2)") (class "Default")
      (node (ref "K4") (pin "2") (pinfunction "COM_2_2") (pintype "bidirectional"))
    )
    (net (code "107") (name "unconnected-(K4-NC-Pad4)") (class "Default")
      (node (ref "K4") (pin "4") (pinfunction "NC_4") (pintype "no_connect"))
    )
    (net (code "108") (name "unconnected-(U1-RS232-Pad15)") (class "Default")
      (node (ref "U1") (pin "15") (pinfunction "RS232_15") (pintype "input"))
    )
    (net (code "109") (name "unconnected-(U1-~{CTS}-Pad9)") (class "Default")
      (node (ref "U1") (pin "9") (pinfunction "~{CTS}_9") (pintype "input"))
    )
    (net (code "110") (name "unconnected-(U1-~{DCD}-Pad12)") (class "Default")
      (node (ref "U1") (pin "12") (pinfunction "~{DCD}_12") (pintype "input"))
    )
    (net (code "111") (name "unconnected-(U1-~{DSR}-Pad10)") (class "Default")
      (node (ref "U1") (pin "10") (pinfunction "~{DSR}_10") (pintype "input"))
    )
    (net (code "112") (name "unconnected-(U1-~{RI}-Pad11)") (class "Default")
      (node (ref "U1") (pin "11") (pinfunction "~{RI}_11") (pintype "input"))
    )
    (net (code "113") (name "unconnected-(U3-IO2-Pad24)") (class "Default")
      (node (ref "U3") (pin "24") (pinfunction "IO2_24") (pintype "bidirectional"))
    )
    (net (code "114") (name "unconnected-(U3-IO4-Pad26)") (class "Default")
      (node (ref "U3") (pin "26") (pinfunction "IO4_26") (pintype "bidirectional"))
    )
    (net (code "115") (name "unconnected-(U3-IO12-Pad14)") (class "Default")
      (node (ref "U3") (pin "14") (pinfunction "IO12_14") (pintype "bidirectional"))
    )
    (net (code "116") (name "unconnected-(U3-IO19-Pad31)") (class "Default")
      (node (ref "U3") (pin "31") (pinfunction "IO19_31") (pintype "bidirectional"))
    )
    (net (code "117") (name "unconnected-(U3-IO23-Pad37)") (class "Default")
      (node (ref "U3") (pin "37") (pinfunction "IO23_37") (pintype "bidirectional"))
    )
    (net (code "118") (name "unconnected-(U3-IO27-Pad12)") (class "Default")
      (node (ref "U3") (pin "12") (pinfunction "IO27_12") (pintype "bidirectional"))
    )
    (net (code "119") (name "unconnected-(U3-IO32-Pad8)") (class "Default")
      (node (ref "U3") (pin "8") (pinfunction "IO32_8") (pintype "bidirectional"))
    )
    (net (code "120") (name "unconnected-(U3-IO33-Pad9)") (class "Default")
      (node (ref "U3") (pin "9") (pinfunction "IO33_9") (pintype "bidirectional"))
    )
    (net (code "121") (name "unconnected-(U3-IO34-Pad6)") (class "Default")
      (node (ref "U3") (pin "6") (pinfunction "IO34_6") (pintype "input"))
    )
    (net (code "122") (name "unconnected-(U3-IO35-Pad7)") (class "Default")
      (node (ref "U3") (pin "7") (pinfunction "IO35_7") (pintype "input"))
    )
    (net (code "123") (name "unconnected-(U3-SCK{slash}CLK-Pad20)") (class "Default")
      (node (ref "U3") (pin "20") (pinfunction "SCK/CLK_20") (pintype "bidirectional"))
    )
    (net (code "124") (name "unconnected-(U3-SCS{slash}CMD-Pad19)") (class "Default")
      (node (ref "U3") (pin "19") (pinfunction "SCS/CMD_19") (pintype "bidirectional"))
    )
    (net (code "125") (name "unconnected-(U3-SDI{slash}SD1-Pad22)") (class "Default")
      (node (ref "U3") (pin "22") (pinfunction "SDI/SD1_22") (pintype "bidirectional"))
    )
    (net (code "126") (name "unconnected-(U3-SDO{slash}SD0-Pad21)") (class "Default")
      (node (ref "U3") (pin "21") (pinfunction "SDO/SD0_21") (pintype "bidirectional"))
    )
    (net (code "127") (name "unconnected-(U3-SENSOR_VN-Pad5)") (class "Default")
      (node (ref "U3") (pin "5") (pinfunction "SENSOR_VN_5") (pintype "input"))
    )
    (net (code "128") (name "unconnected-(U3-SENSOR_VP-Pad4)") (class "Default")
      (node (ref "U3") (pin "4") (pinfunction "SENSOR_VP_4") (pintype "input"))
    )
    (net (code "129") (name "unconnected-(U3-SHD{slash}SD2-Pad17)") (class "Default")
      (node (ref "U3") (pin "17") (pinfunction "SHD/SD2_17") (pintype "bidirectional"))
    )
    (net (code "130") (name "unconnected-(U3-SWP{slash}SD3-Pad18)") (class "Default")
      (node (ref "U3") (pin "18") (pinfunction "SWP/SD3_18") (pintype "bidirectional"))
    )
  )
)
